# USB_SD.net
KiCad netlist of a schematic drawn in Altium Designer
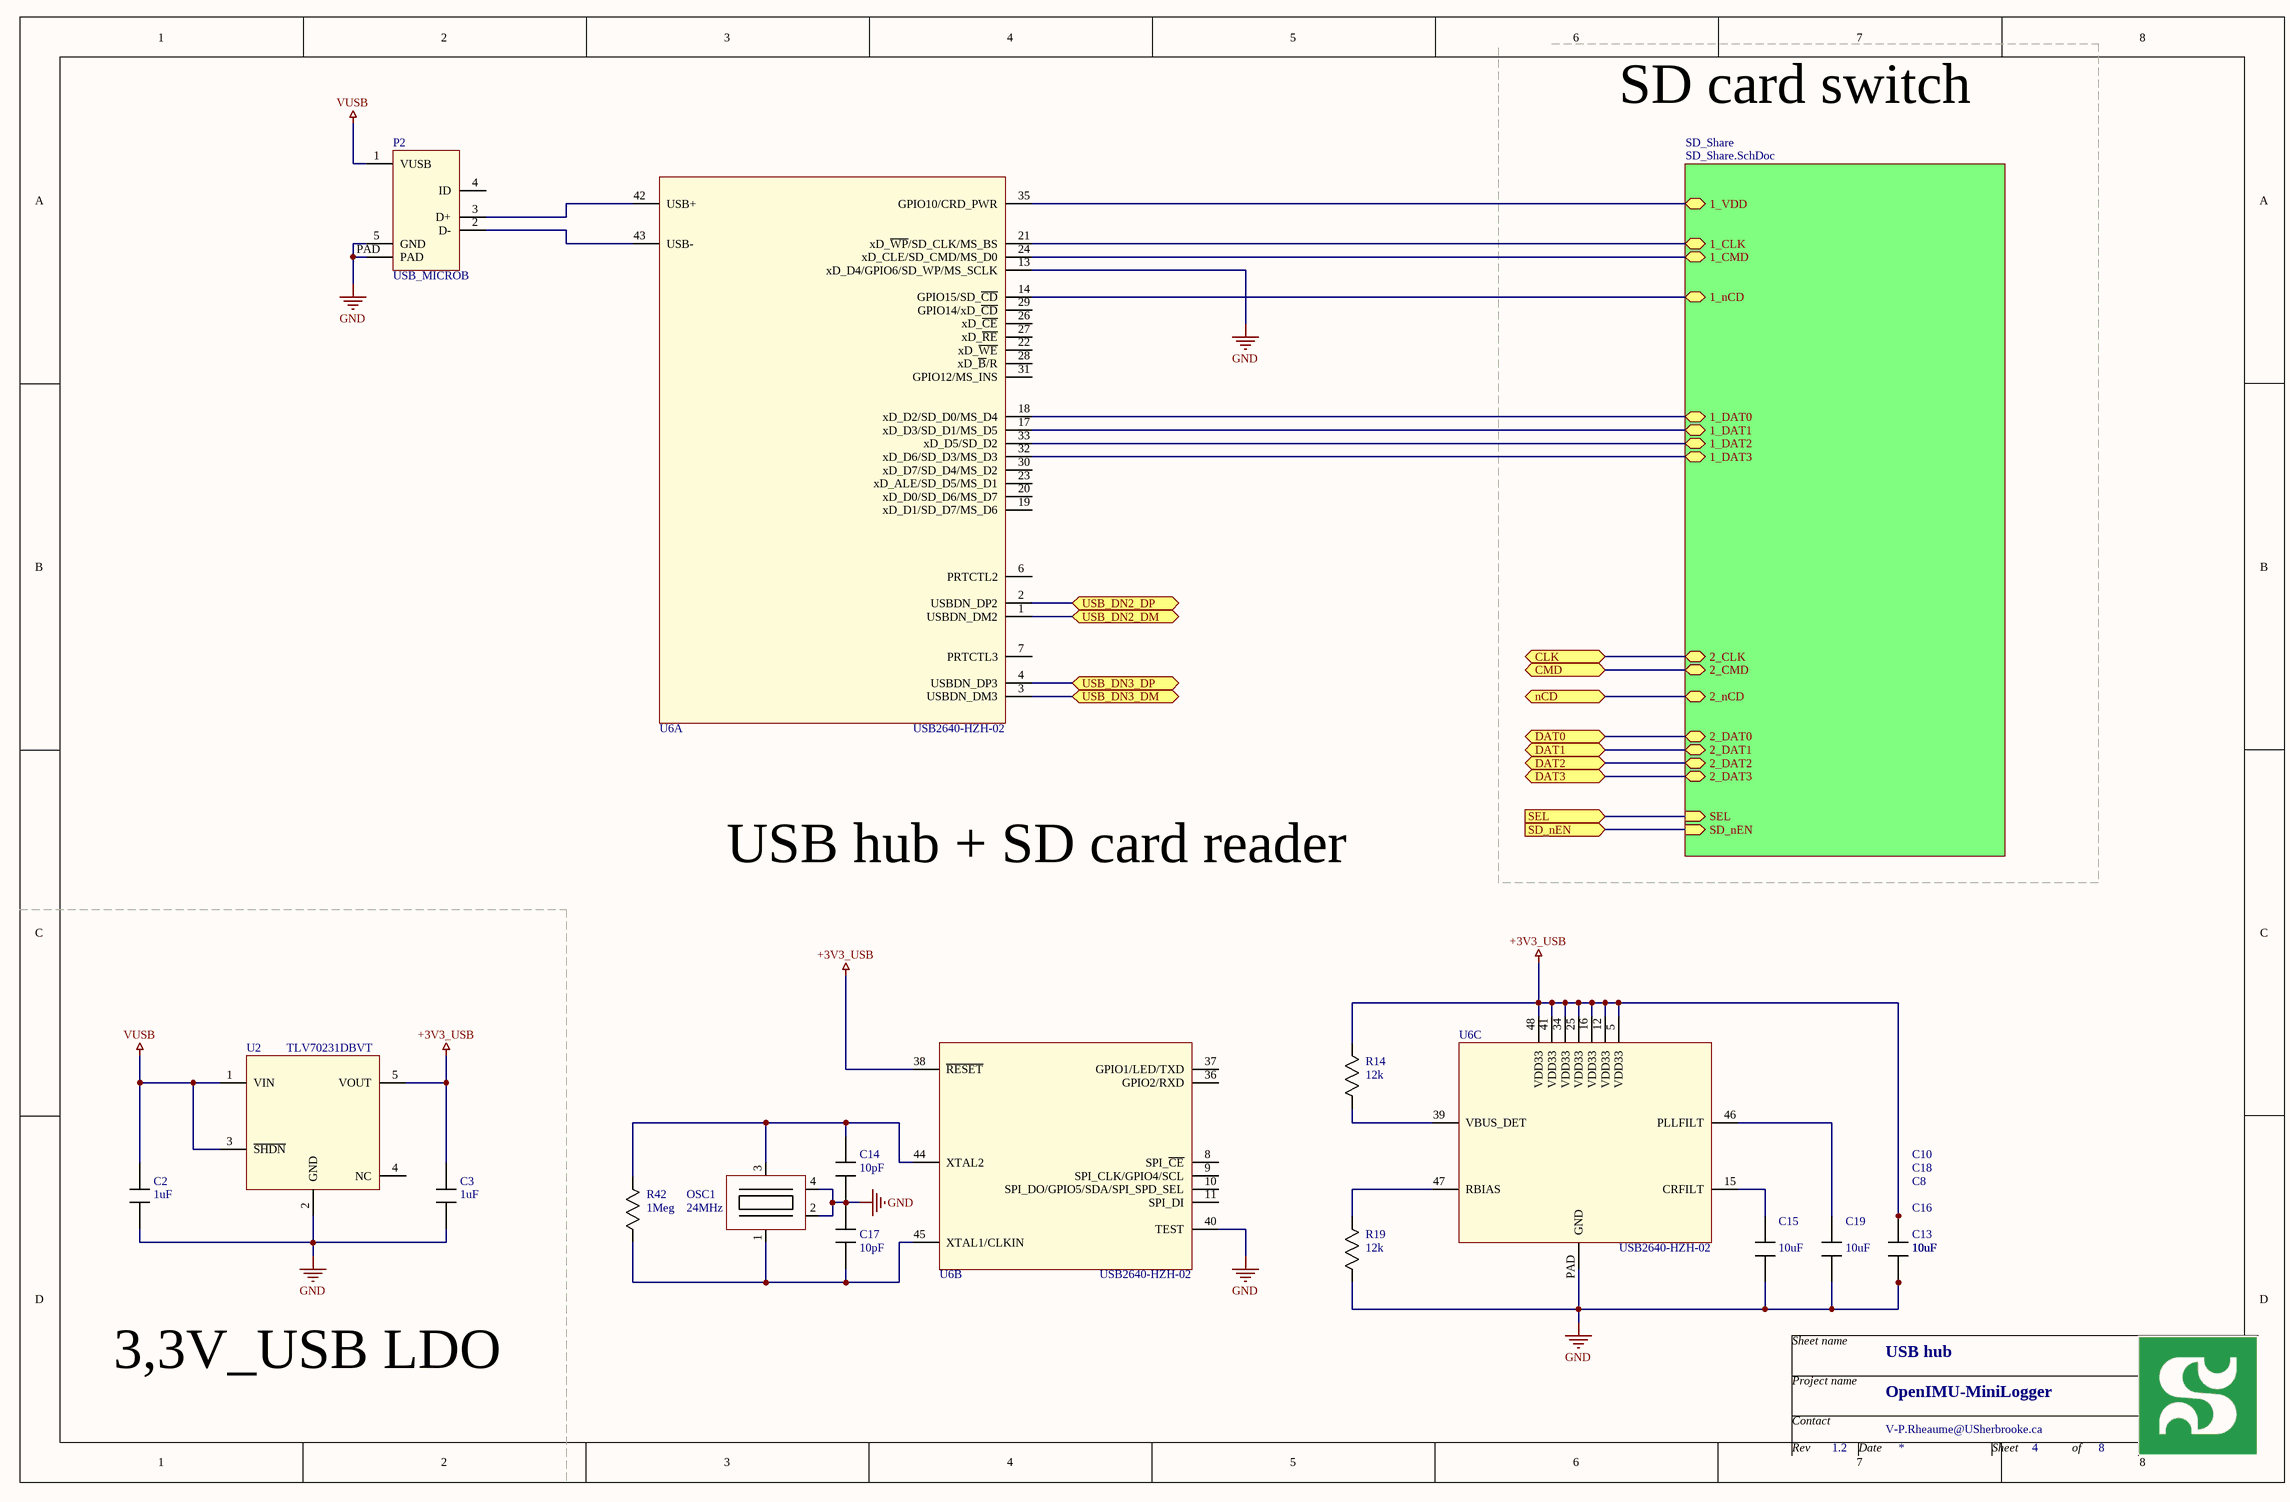
[diagram p0: USB_SD.SchDoc]

(export (version "E")
  (design (tool "Eeschema 10.0.6"))
  (components
    (comp (ref "C2")
      (value "1uF")
      (footprint "0603")
      (description "Capacitor")
      (fields (field (name "MFG") "Samsung"))
      (libsource (lib "INTER_2014") (part "Capacitor"))
    )
    (comp (ref "C3")
      (value "1uF")
      (footprint "0603")
      (description "Capacitor")
      (fields (field (name "MFG") "Samsung"))
      (libsource (lib "INTER_2014") (part "Capacitor"))
    )
    (comp (ref "C8")
      (value "10uF")
      (footprint "0603")
      (description "Capacitor")
      (fields (field (name "MFG") "Murata"))
      (libsource (lib "INTER_2014") (part "Capacitor"))
    )
    (comp (ref "C10")
      (value "10uF")
      (footprint "0603")
      (description "Capacitor")
      (fields (field (name "MFG") "Murata"))
      (libsource (lib "INTER_2014") (part "Capacitor"))
    )
    (comp (ref "C13")
      (value "10uF")
      (footprint "0603")
      (description "Capacitor")
      (fields (field (name "MFG") "Murata"))
      (libsource (lib "INTER_2014") (part "Capacitor"))
    )
    (comp (ref "C14")
      (value "10pF")
      (footprint "0402")
      (description "Capacitor")
      (fields (field (name "MFG") "Wurth"))
      (libsource (lib "INTER_2014") (part "Capacitor"))
    )
    (comp (ref "C15")
      (value "10uF")
      (footprint "0603")
      (description "Capacitor")
      (fields (field (name "MFG") "Murata"))
      (libsource (lib "INTER_2014") (part "Capacitor"))
    )
    (comp (ref "C16")
      (value "10uF")
      (footprint "0603")
      (description "Capacitor")
      (fields (field (name "MFG") "Murata"))
      (libsource (lib "INTER_2014") (part "Capacitor"))
    )
    (comp (ref "C17")
      (value "10pF")
      (footprint "0402")
      (description "Capacitor")
      (fields (field (name "MFG") "Wurth"))
      (libsource (lib "INTER_2014") (part "Capacitor"))
    )
    (comp (ref "C18")
      (value "10uF")
      (footprint "0603")
      (description "Capacitor")
      (fields (field (name "MFG") "Murata"))
      (libsource (lib "INTER_2014") (part "Capacitor"))
    )
    (comp (ref "C19")
      (value "10uF")
      (footprint "0603")
      (description "Capacitor")
      (fields (field (name "MFG") "Murata"))
      (libsource (lib "INTER_2014") (part "Capacitor"))
    )
    (comp (ref "OSC1")
      (value "24MHz")
      (footprint "XTAL_ABM10")
      (description "Crystal")
      (fields (field (name "MFG") "Abracon") (field (name "Comment") "Crystal_4"))
      (libsource (lib "INTER_2014") (part "Crystal_4"))
    )
    (comp (ref "P2")
      (value "USB_MICROB")
      (footprint "USB_MICROB")
      (description "Micro-B USB connector")
      (fields (field (name "MFG") "Amphenol"))
      (libsource (lib "INTER_2014") (part "USB_MICROB"))
    )
    (comp (ref "R14")
      (value "12k")
      (footprint "0402")
      (description "Resistor")
      (fields (field (name "MFG") "Yageo"))
      (libsource (lib "INTER_2014") (part "Resistor"))
    )
    (comp (ref "R19")
      (value "12k")
      (footprint "0402")
      (description "Resistor")
      (fields (field (name "MFG") "Yageo"))
      (libsource (lib "INTER_2014") (part "Resistor"))
    )
    (comp (ref "R42")
      (value "1Meg")
      (footprint "0603")
      (description "Resistor")
      (fields (field (name "MFG") "Stackpole"))
      (libsource (lib "INTER_2014") (part "Resistor"))
    )
    (comp (ref "U2")
      (value "AP2112K-3.3TRG1")
      (footprint "SOT23_5")
      (description "Linear voltage regulator")
      (fields (field (name "MFG") "TI") (field (name "MFG_PN") "TLV70231DBVT"))
      (libsource (lib "INTER_2014") (part "AP2112K-3.3TRG1"))
    )
    (comp (ref "U6")
      (value "USB2640-HZH-02")
      (footprint "QFN48")
      (description "USB2 hub and card reader")
      (fields (field (name "MFG") "Microchip") (field (name "MFG_PN") "USB2640-HZH-02"))
      (libsource (lib "INTER_2014") (part "USB2640-HZH-02"))
    )
  )
  (nets
    (net (code "1") (name "+3V3_USB") (class "Default")
      (node (ref "C10") (pin "1") (pintype "passive"))
      (node (ref "C13") (pin "1") (pintype "passive"))
      (node (ref "C16") (pin "1") (pintype "passive"))
      (node (ref "C18") (pin "1") (pintype "passive"))
      (node (ref "C3") (pin "1") (pintype "passive"))
      (node (ref "C8") (pin "1") (pintype "passive"))
      (node (ref "R14") (pin "1") (pintype "passive"))
      (node (ref "U2") (pin "5") (pinfunction "VOUT_5") (pintype "passive"))
      (node (ref "U6") (pin "12") (pinfunction "VDD33_12") (pintype "passive"))
      (node (ref "U6") (pin "16") (pinfunction "VDD33_16") (pintype "passive"))
      (node (ref "U6") (pin "25") (pinfunction "VDD33_25") (pintype "passive"))
      (node (ref "U6") (pin "34") (pinfunction "VDD33_34") (pintype "passive"))
      (node (ref "U6") (pin "38") (pinfunction "~{RESET}_38") (pintype "passive"))
      (node (ref "U6") (pin "41") (pinfunction "VDD33_41") (pintype "passive"))
      (node (ref "U6") (pin "48") (pinfunction "VDD33_48") (pintype "passive"))
      (node (ref "U6") (pin "5") (pinfunction "VDD33_5") (pintype "passive"))
    )
    (net (code "2") (name "/1_CLK") (class "Default")
      (node (ref "U6") (pin "21") (pinfunction "xD_~{WP}/SD_CLK/MS_BS_21") (pintype "passive"))
    )
    (net (code "3") (name "/1_CMD") (class "Default")
      (node (ref "U6") (pin "24") (pinfunction "xD_CLE/SD_CMD/MS_D0_24") (pintype "passive"))
    )
    (net (code "4") (name "/1_DAT0") (class "Default")
      (node (ref "U6") (pin "18") (pinfunction "xD_D2/SD_D0/MS_D4_18") (pintype "passive"))
    )
    (net (code "5") (name "/1_DAT1") (class "Default")
      (node (ref "U6") (pin "17") (pinfunction "xD_D3/SD_D1/MS_D5_17") (pintype "passive"))
    )
    (net (code "6") (name "/1_DAT2") (class "Default")
      (node (ref "U6") (pin "33") (pinfunction "xD_D5/SD_D2_33") (pintype "passive"))
    )
    (net (code "7") (name "/1_DAT3") (class "Default")
      (node (ref "U6") (pin "32") (pinfunction "xD_D6/SD_D3/MS_D3_32") (pintype "passive"))
    )
    (net (code "8") (name "/1_VDD") (class "Default")
      (node (ref "U6") (pin "35") (pinfunction "GPIO10/CRD_PWR_35") (pintype "passive"))
    )
    (net (code "9") (name "/1_nCD") (class "Default")
      (node (ref "U6") (pin "14") (pinfunction "GPIO15/SD_~{CD}_14") (pintype "passive"))
    )
    (net (code "18") (name "/USB_DN2_DM") (class "Default")
      (node (ref "U6") (pin "1") (pinfunction "USBDN_DM2_1") (pintype "passive"))
    )
    (net (code "19") (name "/USB_DN2_DP") (class "Default")
      (node (ref "U6") (pin "2") (pinfunction "USBDN_DP2_2") (pintype "passive"))
    )
    (net (code "20") (name "/USB_DN3_DM") (class "Default")
      (node (ref "U6") (pin "3") (pinfunction "USBDN_DM3_3") (pintype "passive"))
    )
    (net (code "21") (name "/USB_DN3_DP") (class "Default")
      (node (ref "U6") (pin "4") (pinfunction "USBDN_DP3_4") (pintype "passive"))
    )
    (net (code "23") (name "GND") (class "Default")
      (node (ref "C10") (pin "2") (pintype "passive"))
      (node (ref "C13") (pin "2") (pintype "passive"))
      (node (ref "C14") (pin "2") (pintype "passive"))
      (node (ref "C15") (pin "2") (pintype "passive"))
      (node (ref "C16") (pin "2") (pintype "passive"))
      (node (ref "C17") (pin "1") (pintype "passive"))
      (node (ref "C18") (pin "2") (pintype "passive"))
      (node (ref "C19") (pin "2") (pintype "passive"))
      (node (ref "C2") (pin "2") (pintype "passive"))
      (node (ref "C3") (pin "2") (pintype "passive"))
      (node (ref "C8") (pin "2") (pintype "passive"))
      (node (ref "OSC1") (pin "2") (pintype "passive"))
      (node (ref "OSC1") (pin "4") (pintype "passive"))
      (node (ref "P2") (pin "5") (pinfunction "GND_5") (pintype "passive"))
      (node (ref "P2") (pin "PAD") (pinfunction "PAD_PAD") (pintype "passive"))
      (node (ref "R19") (pin "2") (pintype "passive"))
      (node (ref "U2") (pin "2") (pinfunction "GND_2") (pintype "passive"))
      (node (ref "U6") (pin "13") (pinfunction "xD_D4/GPIO6/SD_WP/MS_SCLK_13") (pintype "passive"))
      (node (ref "U6") (pin "40") (pinfunction "TEST_40") (pintype "passive"))
      (node (ref "U6") (pin "PAD") (pinfunction "GND_PAD") (pintype "passive"))
    )
    (net (code "24") (name "Net-(P2-D+)") (class "Default")
      (node (ref "P2") (pin "3") (pinfunction "D+_3") (pintype "passive"))
      (node (ref "U6") (pin "42") (pinfunction "USB+_42") (pintype "passive"))
    )
    (net (code "25") (name "Net-(P2-D-)") (class "Default")
      (node (ref "P2") (pin "2") (pinfunction "D-_2") (pintype "passive"))
      (node (ref "U6") (pin "43") (pinfunction "USB-_43") (pintype "passive"))
    )
    (net (code "26") (name "Net-(U6B-XTAL1{slash}CLKIN)") (class "Default")
      (node (ref "C17") (pin "2") (pintype "passive"))
      (node (ref "OSC1") (pin "1") (pintype "passive"))
      (node (ref "R42") (pin "2") (pintype "passive"))
      (node (ref "U6") (pin "45") (pinfunction "XTAL1/CLKIN_45") (pintype "passive"))
    )
    (net (code "27") (name "Net-(U6B-XTAL2)") (class "Default")
      (node (ref "C14") (pin "1") (pintype "passive"))
      (node (ref "OSC1") (pin "3") (pintype "passive"))
      (node (ref "R42") (pin "1") (pintype "passive"))
      (node (ref "U6") (pin "44") (pinfunction "XTAL2_44") (pintype "passive"))
    )
    (net (code "28") (name "Net-(U6C-CRFILT)") (class "Default")
      (node (ref "C15") (pin "1") (pintype "passive"))
      (node (ref "U6") (pin "15") (pinfunction "CRFILT_15") (pintype "passive"))
    )
    (net (code "29") (name "Net-(U6C-PLLFILT)") (class "Default")
      (node (ref "C19") (pin "1") (pintype "passive"))
      (node (ref "U6") (pin "46") (pinfunction "PLLFILT_46") (pintype "passive"))
    )
    (net (code "30") (name "Net-(U6C-RBIAS)") (class "Default")
      (node (ref "R19") (pin "1") (pintype "passive"))
      (node (ref "U6") (pin "47") (pinfunction "RBIAS_47") (pintype "passive"))
    )
    (net (code "31") (name "Net-(U6C-VBUS_DET)") (class "Default")
      (node (ref "R14") (pin "2") (pintype "passive"))
      (node (ref "U6") (pin "39") (pinfunction "VBUS_DET_39") (pintype "passive"))
    )
    (net (code "32") (name "VUSB") (class "Default")
      (node (ref "C2") (pin "1") (pintype "passive"))
      (node (ref "P2") (pin "1") (pinfunction "VUSB_1") (pintype "passive"))
      (node (ref "U2") (pin "1") (pinfunction "VIN_1") (pintype "passive"))
      (node (ref "U2") (pin "3") (pinfunction "~{SHDN}_3") (pintype "passive"))
    )
    (net (code "33") (name "unconnected-(P2-ID-Pad4)") (class "Default")
      (node (ref "P2") (pin "4") (pinfunction "ID_4") (pintype "passive"))
    )
    (net (code "34") (name "unconnected-(U2-NC-Pad4)") (class "Default")
      (node (ref "U2") (pin "4") (pinfunction "NC_4") (pintype "passive"))
    )
    (net (code "35") (name "unconnected-(U6A-GPIO12{slash}MS_INS-Pad31)") (class "Default")
      (node (ref "U6") (pin "31") (pinfunction "GPIO12/MS_INS_31") (pintype "passive"))
    )
    (net (code "36") (name "unconnected-(U6A-GPIO14{slash}xD_~{CD}-Pad29)") (class "Default")
      (node (ref "U6") (pin "29") (pinfunction "GPIO14/xD_~{CD}_29") (pintype "passive"))
    )
    (net (code "37") (name "unconnected-(U6A-PRTCTL2-Pad6)") (class "Default")
      (node (ref "U6") (pin "6") (pinfunction "PRTCTL2_6") (pintype "passive"))
    )
    (net (code "38") (name "unconnected-(U6A-PRTCTL3-Pad7)") (class "Default")
      (node (ref "U6") (pin "7") (pinfunction "PRTCTL3_7") (pintype "passive"))
    )
    (net (code "39") (name "unconnected-(U6A-xD_ALE{slash}SD_D5{slash}MS_D1-Pad23)") (class "Default")
      (node (ref "U6") (pin "23") (pinfunction "xD_ALE/SD_D5/MS_D1_23") (pintype "passive"))
    )
    (net (code "40") (name "unconnected-(U6A-xD_D0{slash}SD_D6{slash}MS_D7-Pad20)") (class "Default")
      (node (ref "U6") (pin "20") (pinfunction "xD_D0/SD_D6/MS_D7_20") (pintype "passive"))
    )
    (net (code "41") (name "unconnected-(U6A-xD_D1{slash}SD_D7{slash}MS_D6-Pad19)") (class "Default")
      (node (ref "U6") (pin "19") (pinfunction "xD_D1/SD_D7/MS_D6_19") (pintype "passive"))
    )
    (net (code "42") (name "unconnected-(U6A-xD_D7{slash}SD_D4{slash}MS_D2-Pad30)") (class "Default")
      (node (ref "U6") (pin "30") (pinfunction "xD_D7/SD_D4/MS_D2_30") (pintype "passive"))
    )
    (net (code "43") (name "unconnected-(U6A-xD_~{B}{slash}R-Pad28)") (class "Default")
      (node (ref "U6") (pin "28") (pinfunction "xD_~{B}/R_28") (pintype "passive"))
    )
    (net (code "44") (name "unconnected-(U6A-xD_~{CE}-Pad26)") (class "Default")
      (node (ref "U6") (pin "26") (pinfunction "xD_~{CE}_26") (pintype "passive"))
    )
    (net (code "45") (name "unconnected-(U6A-xD_~{RE}-Pad27)") (class "Default")
      (node (ref "U6") (pin "27") (pinfunction "xD_~{RE}_27") (pintype "passive"))
    )
    (net (code "46") (name "unconnected-(U6A-xD_~{WE}-Pad22)") (class "Default")
      (node (ref "U6") (pin "22") (pinfunction "xD_~{WE}_22") (pintype "passive"))
    )
    (net (code "47") (name "unconnected-(U6B-GPIO1{slash}LED{slash}TXD-Pad37)") (class "Default")
      (node (ref "U6") (pin "37") (pinfunction "GPIO1/LED/TXD_37") (pintype "passive"))
    )
    (net (code "48") (name "unconnected-(U6B-GPIO2{slash}RXD-Pad36)") (class "Default")
      (node (ref "U6") (pin "36") (pinfunction "GPIO2/RXD_36") (pintype "passive"))
    )
    (net (code "49") (name "unconnected-(U6B-SPI_CLK{slash}GPIO4{slash}SCL-Pad9)") (class "Default")
      (node (ref "U6") (pin "9") (pinfunction "SPI_CLK/GPIO4/SCL_9") (pintype "passive"))
    )
    (net (code "50") (name "unconnected-(U6B-SPI_DI-Pad11)") (class "Default")
      (node (ref "U6") (pin "11") (pinfunction "SPI_DI_11") (pintype "passive"))
    )
    (net (code "51") (name "unconnected-(U6B-SPI_DO{slash}GPIO5{slash}SDA{slash}SPI_SPD_SEL-Pad10)") (class "Default")
      (node (ref "U6") (pin "10") (pinfunction "SPI_DO/GPIO5/SDA/SPI_SPD_SEL_10") (pintype "passive"))
    )
    (net (code "52") (name "unconnected-(U6B-SPI_~{CE}-Pad8)") (class "Default")
      (node (ref "U6") (pin "8") (pinfunction "SPI_~{CE}_8") (pintype "passive"))
    )
  )
)
